# LeftPannel.net
KiCad netlist of a schematic drawn in Altium Designer
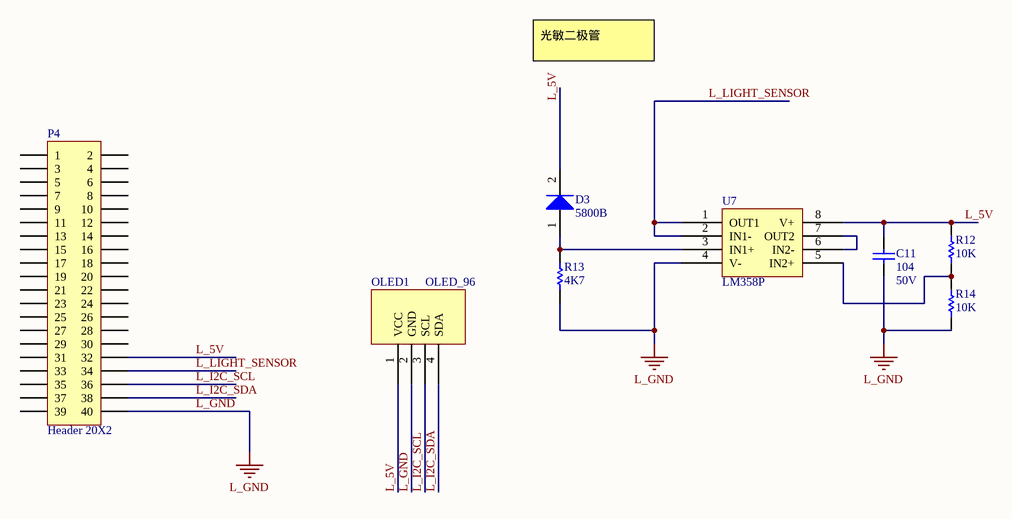
[diagram p0: LeftPannel.SchDoc]

(export (version "E")
  (design (tool "Eeschema 10.0.6"))
  (components
    (comp (ref "C11")
      (value "50V")
      (footprint "NeoIVClock:CAPC1608L")
      (description "Capacitor")
      (fields (field (name "ALTIUM_VALUE") "104") (field (name "PUBLISHER") "Altium Limited"))
      (libsource (lib "Miscellaneous Devices") (part "Cap"))
    )
    (comp (ref "D3")
      (value "5800B")
      (footprint "NeoIVClock:5800B")
      (description "Default Diode")
      (fields (field (name "PUBLISHER") "Altium Limited"))
      (libsource (lib "Miscellaneous Devices") (part "Diode"))
    )
    (comp (ref "OLED1")
      (value "OLED_96")
      (footprint "NeoIVClock:OLED_96")
      (libsource (lib "NeoIVClock") (part "OLED_96"))
    )
    (comp (ref "P4")
      (value "Header 20X2")
      (footprint "HDR2X20")
      (description "Header, 20-Pin, Dual row")
      (fields (field (name "PUBLISHER") "Altium Limited"))
      (libsource (lib "Miscellaneous Connectors") (part "Header 20X2"))
    )
    (comp (ref "R12")
      (value "10K")
      (footprint "NeoIVClock:RESC1608L")
      (description "Resistor")
      (fields (field (name "Comment") "Res1") (field (name "PUBLISHER") "Altium Limited"))
      (libsource (lib "Miscellaneous Devices") (part "Res1"))
    )
    (comp (ref "R13")
      (value "4K7")
      (footprint "NeoIVClock:RESC1608L")
      (description "Resistor")
      (fields (field (name "Comment") "Res1") (field (name "PUBLISHER") "Altium Limited"))
      (libsource (lib "Miscellaneous Devices") (part "Res1"))
    )
    (comp (ref "R14")
      (value "10K")
      (footprint "NeoIVClock:RESC1608L")
      (description "Resistor")
      (fields (field (name "Comment") "Res1") (field (name "PUBLISHER") "Altium Limited"))
      (libsource (lib "Miscellaneous Devices") (part "Res1"))
    )
    (comp (ref "U7") (value "LM358P") (footprint "DIP-8") (libsource (lib "NeoIVClock") (part "LM358P")))
  )
  (nets
    (net (code "1") (name "/L_5V") (class "Default")
      (node (ref "C11") (pin "2") (pinfunction "2_2") (pintype "passive"))
      (node (ref "D3") (pin "2") (pinfunction "K_2") (pintype "passive"))
      (node (ref "OLED1") (pin "1") (pinfunction "VCC_1") (pintype "passive"))
      (node (ref "P4") (pin "32") (pinfunction "32_32") (pintype "passive"))
      (node (ref "R12") (pin "1") (pinfunction "1_1") (pintype "passive"))
      (node (ref "U7") (pin "8") (pinfunction "V+_8") (pintype "passive"))
    )
    (net (code "2") (name "/L_I2C_SCL") (class "Default")
      (node (ref "OLED1") (pin "3") (pinfunction "SCL_3") (pintype "passive"))
      (node (ref "P4") (pin "36") (pinfunction "36_36") (pintype "passive"))
    )
    (net (code "3") (name "/L_I2C_SDA") (class "Default")
      (node (ref "OLED1") (pin "4") (pinfunction "SDA_4") (pintype "passive"))
      (node (ref "P4") (pin "38") (pinfunction "38_38") (pintype "passive"))
    )
    (net (code "4") (name "/L_LIGHT_SENSOR") (class "Default")
      (node (ref "P4") (pin "34") (pinfunction "34_34") (pintype "passive"))
      (node (ref "U7") (pin "1") (pinfunction "OUT1_1") (pintype "passive"))
      (node (ref "U7") (pin "2") (pinfunction "IN1-_2") (pintype "passive"))
    )
    (net (code "5") (name "L_GND") (class "Default")
      (node (ref "C11") (pin "1") (pinfunction "1_1") (pintype "passive"))
      (node (ref "OLED1") (pin "2") (pinfunction "GND_2") (pintype "passive"))
      (node (ref "P4") (pin "40") (pinfunction "40_40") (pintype "passive"))
      (node (ref "R13") (pin "2") (pinfunction "2_2") (pintype "passive"))
      (node (ref "R14") (pin "2") (pinfunction "2_2") (pintype "passive"))
      (node (ref "U7") (pin "4") (pinfunction "V-_4") (pintype "passive"))
    )
    (net (code "6") (name "Net-(D3-A)") (class "Default")
      (node (ref "D3") (pin "1") (pinfunction "A_1") (pintype "passive"))
      (node (ref "R13") (pin "1") (pinfunction "1_1") (pintype "passive"))
      (node (ref "U7") (pin "3") (pinfunction "IN1+_3") (pintype "passive"))
    )
    (net (code "7") (name "Net-(U7-IN2+)") (class "Default")
      (node (ref "R12") (pin "2") (pinfunction "2_2") (pintype "passive"))
      (node (ref "R14") (pin "1") (pinfunction "1_1") (pintype "passive"))
      (node (ref "U7") (pin "5") (pinfunction "IN2+_5") (pintype "passive"))
    )
    (net (code "8") (name "Net-(U7-IN2-)") (class "Default")
      (node (ref "U7") (pin "6") (pinfunction "IN2-_6") (pintype "passive"))
      (node (ref "U7") (pin "7") (pinfunction "OUT2_7") (pintype "passive"))
    )
    (net (code "9") (name "unconnected-(P4-Pad1)") (class "Default")
      (node (ref "P4") (pin "1") (pinfunction "1_1") (pintype "passive"))
    )
    (net (code "10") (name "unconnected-(P4-Pad2)") (class "Default")
      (node (ref "P4") (pin "2") (pinfunction "2_2") (pintype "passive"))
    )
    (net (code "11") (name "unconnected-(P4-Pad3)") (class "Default")
      (node (ref "P4") (pin "3") (pinfunction "3_3") (pintype "passive"))
    )
    (net (code "12") (name "unconnected-(P4-Pad4)") (class "Default")
      (node (ref "P4") (pin "4") (pinfunction "4_4") (pintype "passive"))
    )
    (net (code "13") (name "unconnected-(P4-Pad5)") (class "Default")
      (node (ref "P4") (pin "5") (pinfunction "5_5") (pintype "passive"))
    )
    (net (code "14") (name "unconnected-(P4-Pad6)") (class "Default")
      (node (ref "P4") (pin "6") (pinfunction "6_6") (pintype "passive"))
    )
    (net (code "15") (name "unconnected-(P4-Pad7)") (class "Default")
      (node (ref "P4") (pin "7") (pinfunction "7_7") (pintype "passive"))
    )
    (net (code "16") (name "unconnected-(P4-Pad8)") (class "Default")
      (node (ref "P4") (pin "8") (pinfunction "8_8") (pintype "passive"))
    )
    (net (code "17") (name "unconnected-(P4-Pad9)") (class "Default")
      (node (ref "P4") (pin "9") (pinfunction "9_9") (pintype "passive"))
    )
    (net (code "18") (name "unconnected-(P4-Pad10)") (class "Default")
      (node (ref "P4") (pin "10") (pinfunction "10_10") (pintype "passive"))
    )
    (net (code "19") (name "unconnected-(P4-Pad11)") (class "Default")
      (node (ref "P4") (pin "11") (pinfunction "11_11") (pintype "passive"))
    )
    (net (code "20") (name "unconnected-(P4-Pad12)") (class "Default")
      (node (ref "P4") (pin "12") (pinfunction "12_12") (pintype "passive"))
    )
    (net (code "21") (name "unconnected-(P4-Pad13)") (class "Default")
      (node (ref "P4") (pin "13") (pinfunction "13_13") (pintype "passive"))
    )
    (net (code "22") (name "unconnected-(P4-Pad14)") (class "Default")
      (node (ref "P4") (pin "14") (pinfunction "14_14") (pintype "passive"))
    )
    (net (code "23") (name "unconnected-(P4-Pad15)") (class "Default")
      (node (ref "P4") (pin "15") (pinfunction "15_15") (pintype "passive"))
    )
    (net (code "24") (name "unconnected-(P4-Pad16)") (class "Default")
      (node (ref "P4") (pin "16") (pinfunction "16_16") (pintype "passive"))
    )
    (net (code "25") (name "unconnected-(P4-Pad17)") (class "Default")
      (node (ref "P4") (pin "17") (pinfunction "17_17") (pintype "passive"))
    )
    (net (code "26") (name "unconnected-(P4-Pad18)") (class "Default")
      (node (ref "P4") (pin "18") (pinfunction "18_18") (pintype "passive"))
    )
    (net (code "27") (name "unconnected-(P4-Pad19)") (class "Default")
      (node (ref "P4") (pin "19") (pinfunction "19_19") (pintype "passive"))
    )
    (net (code "28") (name "unconnected-(P4-Pad20)") (class "Default")
      (node (ref "P4") (pin "20") (pinfunction "20_20") (pintype "passive"))
    )
    (net (code "29") (name "unconnected-(P4-Pad21)") (class "Default")
      (node (ref "P4") (pin "21") (pinfunction "21_21") (pintype "passive"))
    )
    (net (code "30") (name "unconnected-(P4-Pad22)") (class "Default")
      (node (ref "P4") (pin "22") (pinfunction "22_22") (pintype "passive"))
    )
    (net (code "31") (name "unconnected-(P4-Pad23)") (class "Default")
      (node (ref "P4") (pin "23") (pinfunction "23_23") (pintype "passive"))
    )
    (net (code "32") (name "unconnected-(P4-Pad24)") (class "Default")
      (node (ref "P4") (pin "24") (pinfunction "24_24") (pintype "passive"))
    )
    (net (code "33") (name "unconnected-(P4-Pad25)") (class "Default")
      (node (ref "P4") (pin "25") (pinfunction "25_25") (pintype "passive"))
    )
    (net (code "34") (name "unconnected-(P4-Pad26)") (class "Default")
      (node (ref "P4") (pin "26") (pinfunction "26_26") (pintype "passive"))
    )
    (net (code "35") (name "unconnected-(P4-Pad27)") (class "Default")
      (node (ref "P4") (pin "27") (pinfunction "27_27") (pintype "passive"))
    )
    (net (code "36") (name "unconnected-(P4-Pad28)") (class "Default")
      (node (ref "P4") (pin "28") (pinfunction "28_28") (pintype "passive"))
    )
    (net (code "37") (name "unconnected-(P4-Pad29)") (class "Default")
      (node (ref "P4") (pin "29") (pinfunction "29_29") (pintype "passive"))
    )
    (net (code "38") (name "unconnected-(P4-Pad30)") (class "Default")
      (node (ref "P4") (pin "30") (pinfunction "30_30") (pintype "passive"))
    )
    (net (code "39") (name "unconnected-(P4-Pad31)") (class "Default")
      (node (ref "P4") (pin "31") (pinfunction "31_31") (pintype "passive"))
    )
    (net (code "40") (name "unconnected-(P4-Pad33)") (class "Default")
      (node (ref "P4") (pin "33") (pinfunction "33_33") (pintype "passive"))
    )
    (net (code "41") (name "unconnected-(P4-Pad35)") (class "Default")
      (node (ref "P4") (pin "35") (pinfunction "35_35") (pintype "passive"))
    )
    (net (code "42") (name "unconnected-(P4-Pad37)") (class "Default")
      (node (ref "P4") (pin "37") (pinfunction "37_37") (pintype "passive"))
    )
    (net (code "43") (name "unconnected-(P4-Pad39)") (class "Default")
      (node (ref "P4") (pin "39") (pinfunction "39_39") (pintype "passive"))
    )
  )
)
